# Peripheral2.net
KiCad netlist of a schematic drawn in Altium Designer
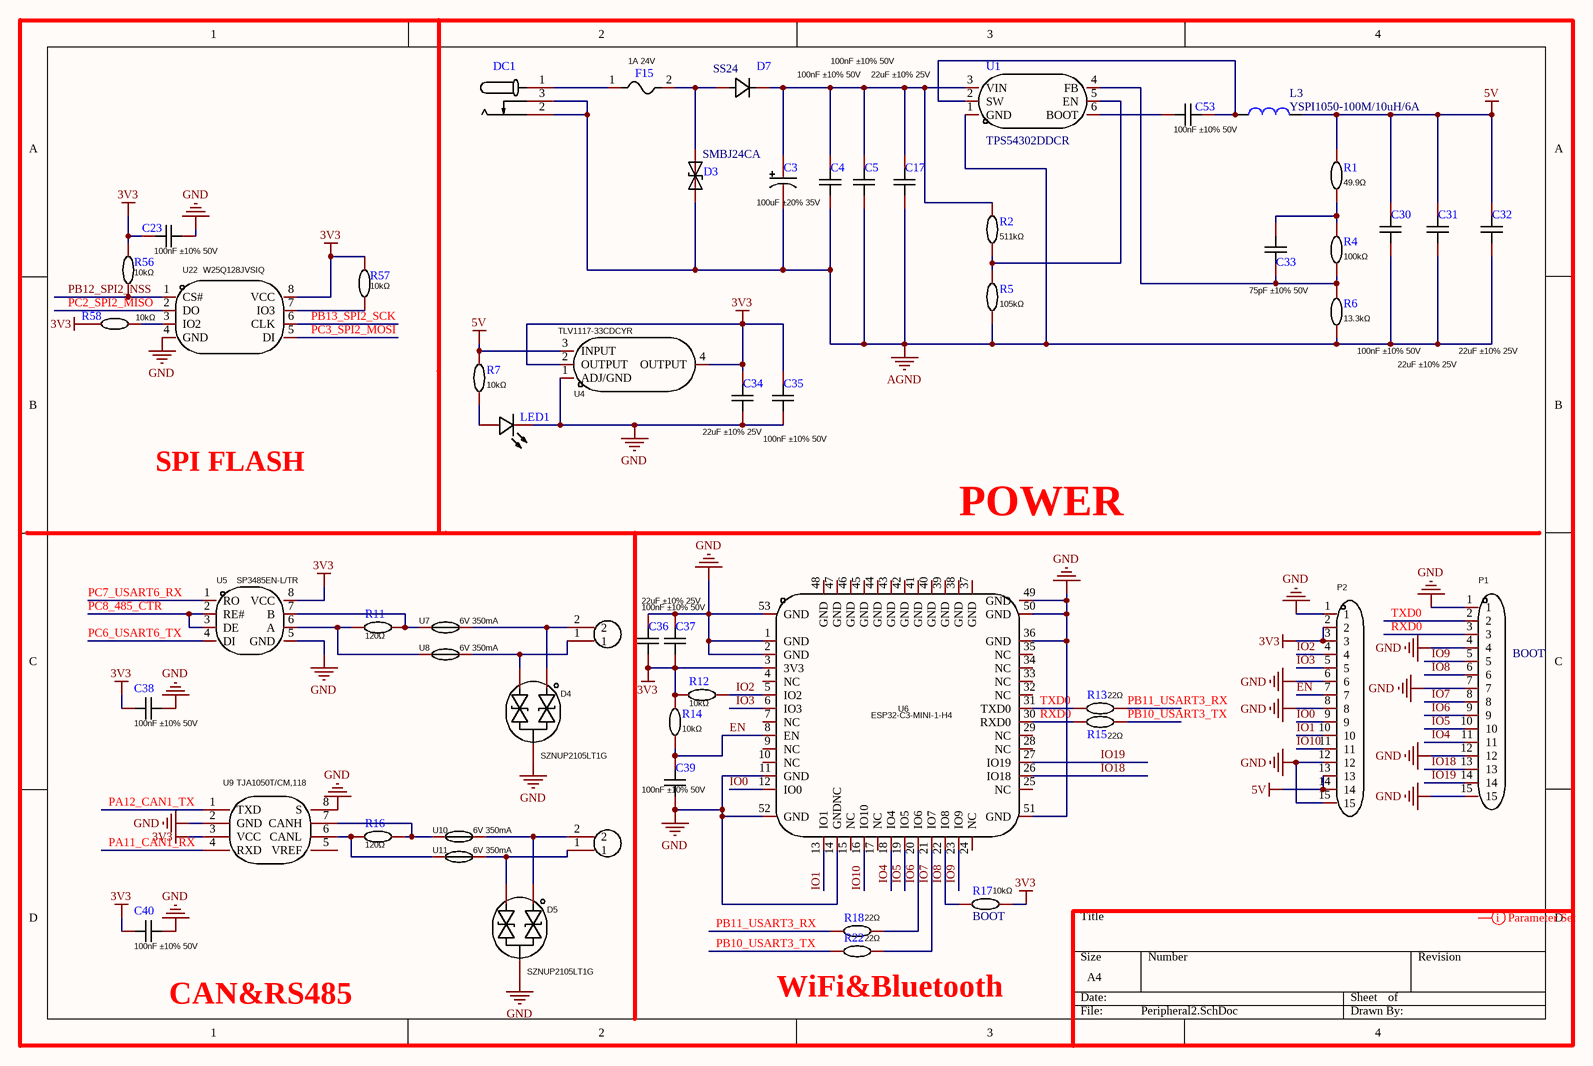
[diagram p0: Peripheral2.SchDoc]

(export (version "E")
  (design (tool "Eeschema 10.0.6"))
  (components
    (comp (ref "C3")
      (value "VES101M1VTR-0607")
      (footprint "CE 6.3*7.7")
      (fields
        (field (name "LCSC PART NAME") "100uF ±20% 35V")
        (field (name "MANUFACTURER") "lelon(立隆)")
        (field (name "TOLERANCE") "±20%")
      )
      (libsource (lib "altium-import") (part "root_0_VES101M1VTR-0607_"))
    )
    (comp (ref "C4")
      (value "CC0603KRX7R9BB104")
      (footprint "C0603")
      (fields
        (field (name "LCSC PART NAME") "100nF ±10% 50V")
        (field (name "MANUFACTURER") "YAGEO(国巨)")
        (field (name "TOLERANCE") "±10%")
      )
      (libsource (lib "altium-import") (part "root_1_CC0603KRX7R9BB104_"))
    )
    (comp (ref "C5")
      (value "CC0603KRX7R9BB104")
      (footprint "C0603")
      (fields
        (field (name "LCSC PART NAME") "100nF ±10% 50V")
        (field (name "MANUFACTURER") "YAGEO(国巨)")
        (field (name "TOLERANCE") "±10%")
      )
      (libsource (lib "altium-import") (part "root_1_CC0603KRX7R9BB104_"))
    )
    (comp (ref "C17")
      (value "CC0603KRX7R9BB104")
      (footprint "C1210")
      (fields
        (field (name "LCSC PART NAME") "22uF ±10% 25V")
        (field (name "MANUFACTURER") "YAGEO(国巨)")
        (field (name "TOLERANCE") "±10%")
      )
      (libsource (lib "altium-import") (part "root_1_CC0603KRX7R9BB104_"))
    )
    (comp (ref "C23")
      (value "CC0603KRX7R9BB104")
      (footprint "C0603")
      (fields
        (field (name "LCSC PART NAME") "100nF ±10% 50V")
        (field (name "MANUFACTURER") "YAGEO(国巨)")
        (field (name "TOLERANCE") "±10%")
      )
      (libsource (lib "altium-import") (part "root_2_CC0603KRX7R9BB104_"))
    )
    (comp (ref "C30")
      (value "CC0603KRX7R9BB104")
      (footprint "C0603")
      (fields
        (field (name "LCSC PART NAME") "100nF ±10% 50V")
        (field (name "MANUFACTURER") "YAGEO(国巨)")
        (field (name "TOLERANCE") "±10%")
      )
      (libsource (lib "altium-import") (part "root_1_CC0603KRX7R9BB104_"))
    )
    (comp (ref "C31")
      (value "CC0603KRX7R9BB104")
      (footprint "C1210")
      (fields
        (field (name "LCSC PART NAME") "22uF ±10% 25V")
        (field (name "MANUFACTURER") "YAGEO(国巨)")
        (field (name "TOLERANCE") "±10%")
      )
      (libsource (lib "altium-import") (part "root_1_CC0603KRX7R9BB104_"))
    )
    (comp (ref "C32")
      (value "CC0603KRX7R9BB104")
      (footprint "C1210")
      (fields
        (field (name "LCSC PART NAME") "22uF ±10% 25V")
        (field (name "MANUFACTURER") "YAGEO(国巨)")
        (field (name "TOLERANCE") "±10%")
      )
      (libsource (lib "altium-import") (part "root_1_CC0603KRX7R9BB104_"))
    )
    (comp (ref "C33")
      (value "CC0603KRX7R9BB104")
      (footprint "C0603")
      (fields
        (field (name "LCSC PART NAME") "75pF ±10% 50V")
        (field (name "MANUFACTURER") "YAGEO(国巨)")
        (field (name "TOLERANCE") "±10%")
      )
      (libsource (lib "altium-import") (part "root_1_CC0603KRX7R9BB104_"))
    )
    (comp (ref "C34")
      (value "CC0603KRX7R9BB104")
      (footprint "C1210")
      (fields
        (field (name "LCSC PART NAME") "22uF ±10% 25V")
        (field (name "MANUFACTURER") "YAGEO(国巨)")
        (field (name "TOLERANCE") "±10%")
      )
      (libsource (lib "altium-import") (part "root_1_CC0603KRX7R9BB104_"))
    )
    (comp (ref "C35")
      (value "CC0603KRX7R9BB104")
      (footprint "C0603")
      (fields
        (field (name "LCSC PART NAME") "100nF ±10% 50V")
        (field (name "MANUFACTURER") "YAGEO(国巨)")
        (field (name "TOLERANCE") "±10%")
      )
      (libsource (lib "altium-import") (part "root_1_CC0603KRX7R9BB104_"))
    )
    (comp (ref "C36")
      (value "CC0603KRX7R9BB104")
      (footprint "C1210")
      (fields
        (field (name "LCSC PART NAME") "22uF ±10% 25V")
        (field (name "MANUFACTURER") "YAGEO(国巨)")
        (field (name "TOLERANCE") "±10%")
      )
      (libsource (lib "altium-import") (part "root_1_CC0603KRX7R9BB104_"))
    )
    (comp (ref "C37")
      (value "CC0603KRX7R9BB104")
      (footprint "C0603")
      (fields
        (field (name "LCSC PART NAME") "100nF ±10% 50V")
        (field (name "MANUFACTURER") "YAGEO(国巨)")
        (field (name "TOLERANCE") "±10%")
      )
      (libsource (lib "altium-import") (part "root_1_CC0603KRX7R9BB104_"))
    )
    (comp (ref "C38")
      (value "CC0603KRX7R9BB104")
      (footprint "C0603")
      (fields
        (field (name "LCSC PART NAME") "100nF ±10% 50V")
        (field (name "MANUFACTURER") "YAGEO(国巨)")
        (field (name "TOLERANCE") "±10%")
      )
      (libsource (lib "altium-import") (part "root_2_CC0603KRX7R9BB104_"))
    )
    (comp (ref "C39")
      (value "CC0603KRX7R9BB104")
      (footprint "C0603")
      (fields
        (field (name "LCSC PART NAME") "100nF ±10% 50V")
        (field (name "MANUFACTURER") "YAGEO(国巨)")
        (field (name "TOLERANCE") "±10%")
      )
      (libsource (lib "altium-import") (part "root_1_CC0603KRX7R9BB104_"))
    )
    (comp (ref "C40")
      (value "CC0603KRX7R9BB104")
      (footprint "C0603")
      (fields
        (field (name "LCSC PART NAME") "100nF ±10% 50V")
        (field (name "MANUFACTURER") "YAGEO(国巨)")
        (field (name "TOLERANCE") "±10%")
      )
      (libsource (lib "altium-import") (part "root_2_CC0603KRX7R9BB104_"))
    )
    (comp (ref "C53")
      (value "CC0603KRX7R9BB104")
      (footprint "C0603")
      (fields
        (field (name "LCSC PART NAME") "100nF ±10% 50V")
        (field (name "MANUFACTURER") "YAGEO(国巨)")
        (field (name "TOLERANCE") "±10%")
      )
      (libsource (lib "altium-import") (part "root_2_CC0603KRX7R9BB104_"))
    )
    (comp (ref "CN1")
      (value "XH-2A_C20079")
      (footprint "XH2.5-2")
      (fields (field (name "MANUFACTURER") "BOOMELE(博穆精密)") (field (name "MANUFACTURER PART") "XH-2A"))
      (libsource (lib "altium-import") (part "root_2_XH-2A_C20079_"))
    )
    (comp (ref "CN2")
      (value "XH-2A_C20079")
      (footprint "XH2.5-2")
      (fields (field (name "MANUFACTURER") "BOOMELE(博穆精密)") (field (name "MANUFACTURER PART") "XH-2A"))
      (libsource (lib "altium-import") (part "root_2_XH-2A_C20079_"))
    )
    (comp (ref "D3")
      (value "SMBJ24CA")
      (footprint "SMB")
      (fields (field (name "MANUFACTURER") "Brightking(君耀电子)"))
      (libsource (lib "altium-import") (part "root_1_SMBJ24CA_C78416_"))
    )
    (comp (ref "D4")
      (value "SZNUP2105LT1G")
      (footprint "SOT-23")
      (fields (field (name "NAME") "SZNUP2105LT1G") (field (name "MANUFACTURER") "onsemi(安森美)"))
      (libsource (lib "altium-import") (part "root_2_SZNUP2105LT1G_"))
    )
    (comp (ref "D5")
      (value "SZNUP2105LT1G")
      (footprint "SOT-23")
      (fields (field (name "NAME") "SZNUP2105LT1G") (field (name "MANUFACTURER") "onsemi(安森美)"))
      (libsource (lib "altium-import") (part "root_2_SZNUP2105LT1G_"))
    )
    (comp (ref "D7")
      (value "SS24")
      (footprint "SMA")
      (fields (field (name "MANUFACTURER") "CJ(江苏长电/长晶)"))
      (libsource (lib "altium-import") (part "root_2_SS24_C2829443_"))
    )
    (comp (ref "DC1")
      (value "DC-005-25A")
      (footprint "DC-005")
      (fields (field (name "MANUFACTURER") "韩国韩荣"))
      (libsource (lib "altium-import") (part "root_0_DC-005-25A_"))
    )
    (comp (ref "F15")
      (value "TLC-NSMD100/24")
      (footprint "F1206")
      (fields (field (name "LCSC PART NAME") "1A 24V") (field (name "MANUFACTURER") "TLC(竞沃)"))
      (libsource (lib "altium-import") (part "root_0_TLC-NSMD100/24_"))
    )
    (comp (ref "L3")
      (value "YSPI1050-100M/10uH/6A")
      (footprint "IND-SMD_L11.5-W10.0_SMMS1040")
      (libsource (lib "*") (part "INDUCTOR"))
    )
    (comp (ref "LED1")
      (value "17-21SYGC/S530-E3/TR8")
      (footprint "LED 0805G")
      (fields (field (name "MANUFACTURER") "EVERLIGHT(亿光)"))
      (libsource (lib "altium-import") (part "root_2_17-21SYGC/S530-E3/TR8_"))
    )
    (comp (ref "P1")
      (value "KH-2.54FH-1X15P-H8.5")
      (footprint "HDR2.54-M-LI-15P")
      (fields (field (name "MANUFACTURER") "kinghelm(金航标)"))
      (libsource (lib "altium-import") (part "root_0_KH-2.54FH-1X15P-H8.5_"))
    )
    (comp (ref "P2")
      (value "KH-2.54FH-1X15P-H8.5")
      (footprint "HDR2.54-M-LI-15P")
      (fields (field (name "MANUFACTURER") "kinghelm(金航标)"))
      (libsource (lib "altium-import") (part "root_0_KH-2.54FH-1X15P-H8.5_"))
    )
    (comp (ref "R1")
      (value "49.9Ω")
      (footprint "R0603")
      (fields
        (field (name "MANUFACTURER") "UNI-ROYAL(厚声)")
        (field (name "MANUFACTURER PART") "0603WAF5113T5E")
        (field (name "TOLERANCE") "±1%")
      )
      (libsource (lib "altium-import") (part "root_1_0603WAF5113T5E_"))
    )
    (comp (ref "R2")
      (value "511kΩ")
      (footprint "R0603")
      (fields
        (field (name "MANUFACTURER") "UNI-ROYAL(厚声)")
        (field (name "MANUFACTURER PART") "0603WAF5113T5E")
        (field (name "TOLERANCE") "±1%")
      )
      (libsource (lib "altium-import") (part "root_1_0603WAF5113T5E_"))
    )
    (comp (ref "R4")
      (value "100kΩ")
      (footprint "R0603")
      (fields
        (field (name "MANUFACTURER") "UNI-ROYAL(厚声)")
        (field (name "MANUFACTURER PART") "0603WAF5113T5E")
        (field (name "TOLERANCE") "±1%")
      )
      (libsource (lib "altium-import") (part "root_1_0603WAF5113T5E_"))
    )
    (comp (ref "R5")
      (value "105kΩ")
      (footprint "R0603")
      (fields
        (field (name "MANUFACTURER") "UNI-ROYAL(厚声)")
        (field (name "MANUFACTURER PART") "0603WAF5113T5E")
        (field (name "TOLERANCE") "±1%")
      )
      (libsource (lib "altium-import") (part "root_1_0603WAF5113T5E_"))
    )
    (comp (ref "R6")
      (value "13.3kΩ")
      (footprint "R0603")
      (fields
        (field (name "MANUFACTURER") "UNI-ROYAL(厚声)")
        (field (name "MANUFACTURER PART") "0603WAF5113T5E")
        (field (name "TOLERANCE") "±1%")
      )
      (libsource (lib "altium-import") (part "root_1_0603WAF5113T5E_"))
    )
    (comp (ref "R7")
      (value "10kΩ")
      (footprint "R0603")
      (fields
        (field (name "MANUFACTURER") "UNI-ROYAL(厚声)")
        (field (name "MANUFACTURER PART") "0603WAF5113T5E")
        (field (name "TOLERANCE") "±1%")
      )
      (libsource (lib "altium-import") (part "root_1_0603WAF5113T5E_"))
    )
    (comp (ref "R11")
      (value "120Ω")
      (footprint "R0603")
      (fields
        (field (name "MANUFACTURER") "UNI-ROYAL(厚声)")
        (field (name "MANUFACTURER PART") "0603WAF5113T5E")
        (field (name "TOLERANCE") "±1%")
      )
      (libsource (lib "altium-import") (part "root_2_0603WAF5113T5E_"))
    )
    (comp (ref "R12")
      (value "10kΩ")
      (footprint "R0603")
      (fields
        (field (name "MANUFACTURER") "UNI-ROYAL(厚声)")
        (field (name "MANUFACTURER PART") "0603WAF5113T5E")
        (field (name "TOLERANCE") "±1%")
      )
      (libsource (lib "altium-import") (part "root_2_0603WAF5113T5E_"))
    )
    (comp (ref "R13")
      (value "22Ω")
      (footprint "R0603")
      (fields
        (field (name "MANUFACTURER") "UNI-ROYAL(厚声)")
        (field (name "MANUFACTURER PART") "0603WAF5113T5E")
        (field (name "TOLERANCE") "±1%")
      )
      (libsource (lib "altium-import") (part "root_2_0603WAF5113T5E_"))
    )
    (comp (ref "R14")
      (value "10kΩ")
      (footprint "R0603")
      (fields
        (field (name "MANUFACTURER") "UNI-ROYAL(厚声)")
        (field (name "MANUFACTURER PART") "0603WAF5113T5E")
        (field (name "TOLERANCE") "±1%")
      )
      (libsource (lib "altium-import") (part "root_1_0603WAF5113T5E_"))
    )
    (comp (ref "R15")
      (value "22Ω")
      (footprint "R0603")
      (fields
        (field (name "MANUFACTURER") "UNI-ROYAL(厚声)")
        (field (name "MANUFACTURER PART") "0603WAF5113T5E")
        (field (name "TOLERANCE") "±1%")
      )
      (libsource (lib "altium-import") (part "root_2_0603WAF5113T5E_"))
    )
    (comp (ref "R16")
      (value "120Ω")
      (footprint "R0603")
      (fields
        (field (name "MANUFACTURER") "UNI-ROYAL(厚声)")
        (field (name "MANUFACTURER PART") "0603WAF5113T5E")
        (field (name "TOLERANCE") "±1%")
      )
      (libsource (lib "altium-import") (part "root_2_0603WAF5113T5E_"))
    )
    (comp (ref "R17")
      (value "10kΩ")
      (footprint "R0603")
      (fields
        (field (name "MANUFACTURER") "UNI-ROYAL(厚声)")
        (field (name "MANUFACTURER PART") "0603WAF5113T5E")
        (field (name "TOLERANCE") "±1%")
      )
      (libsource (lib "altium-import") (part "root_2_0603WAF5113T5E_"))
    )
    (comp (ref "R18")
      (value "22Ω")
      (footprint "R0603")
      (fields
        (field (name "MANUFACTURER") "UNI-ROYAL(厚声)")
        (field (name "MANUFACTURER PART") "0603WAF5113T5E")
        (field (name "TOLERANCE") "±1%")
      )
      (libsource (lib "altium-import") (part "root_2_0603WAF5113T5E_"))
    )
    (comp (ref "R22")
      (value "22Ω")
      (footprint "R0603")
      (fields
        (field (name "MANUFACTURER") "UNI-ROYAL(厚声)")
        (field (name "MANUFACTURER PART") "0603WAF5113T5E")
        (field (name "TOLERANCE") "±1%")
      )
      (libsource (lib "altium-import") (part "root_2_0603WAF5113T5E_"))
    )
    (comp (ref "R56")
      (value "10kΩ")
      (footprint "R0603")
      (fields
        (field (name "MANUFACTURER") "UNI-ROYAL(厚声)")
        (field (name "MANUFACTURER PART") "0603WAF5113T5E")
        (field (name "TOLERANCE") "±1%")
      )
      (libsource (lib "altium-import") (part "root_3_0603WAF5113T5E_"))
    )
    (comp (ref "R57")
      (value "10kΩ")
      (footprint "R0603")
      (fields
        (field (name "MANUFACTURER") "UNI-ROYAL(厚声)")
        (field (name "MANUFACTURER PART") "0603WAF5113T5E")
        (field (name "TOLERANCE") "±1%")
      )
      (libsource (lib "altium-import") (part "root_3_0603WAF5113T5E_"))
    )
    (comp (ref "R58")
      (value "10kΩ")
      (footprint "R0603")
      (fields
        (field (name "MANUFACTURER") "UNI-ROYAL(厚声)")
        (field (name "MANUFACTURER PART") "0603WAF5113T5E")
        (field (name "TOLERANCE") "±1%")
      )
      (libsource (lib "altium-import") (part "root_2_0603WAF5113T5E_"))
    )
    (comp (ref "U1")
      (value "TPS54302DDCR")
      (footprint "SOT23-6")
      (fields (field (name "MANUFACTURER") "TI(德州仪器)"))
      (libsource (lib "altium-import") (part "root_2_mirrored_TPS54302DDCR_"))
    )
    (comp (ref "U4")
      (value "TLV1117-33CDCYR")
      (footprint "SOT223")
      (fields (field (name "NAME") "TLV1117-33CDCYR") (field (name "MANUFACTURER") "TI(德州仪器)"))
      (libsource (lib "altium-import") (part "root_1_mirrored_TLV1117-33CDCYR_"))
    )
    (comp (ref "U5")
      (value "SP3485EN-L/TR")
      (footprint "SOP8_SP3485")
      (fields (field (name "NAME") "SP3485EN-L/TR") (field (name "MANUFACTURER") "MaxLinear"))
      (libsource (lib "altium-import") (part "root_0_SP3485EN-L/TR_"))
    )
    (comp (ref "U6")
      (value "ESP32-C3-MINI-1-H4")
      (footprint "WIFIM-SMD_ESP32-C3-MINI-1")
      (fields (field (name "NAME") "ESP32-C3-MINI-1-H4") (field (name "MANUFACTURER") "ESPRESSIF(乐鑫)"))
      (libsource (lib "altium-import") (part "root_0_ESP32-C3-MINI-1U-H4_"))
    )
    (comp (ref "U7")
      (value "0603L035YR")
      (footprint "F0603")
      (fields (field (name "LCSC PART NAME") "6V 350mA") (field (name "MANUFACTURER") "Littelfuse(美国力特)"))
      (libsource (lib "altium-import") (part "root_0_0603L035YR_"))
    )
    (comp (ref "U8")
      (value "0603L035YR")
      (footprint "F0603")
      (fields (field (name "LCSC PART NAME") "6V 350mA") (field (name "MANUFACTURER") "Littelfuse(美国力特)"))
      (libsource (lib "altium-import") (part "root_0_0603L035YR_"))
    )
    (comp (ref "U9")
      (value "TJA1050T/CM,118")
      (footprint "SOP8_TJA1050")
      (fields (field (name "NAME") "TJA1050T/CM,118") (field (name "MANUFACTURER") "NXP(恩智浦)"))
      (libsource (lib "altium-import") (part "root_0_TJA1050T/CM,118_"))
    )
    (comp (ref "U10")
      (value "0603L035YR")
      (footprint "F0603")
      (fields (field (name "LCSC PART NAME") "6V 350mA") (field (name "MANUFACTURER") "Littelfuse(美国力特)"))
      (libsource (lib "altium-import") (part "root_0_0603L035YR_"))
    )
    (comp (ref "U11")
      (value "0603L035YR")
      (footprint "F0603")
      (fields (field (name "LCSC PART NAME") "6V 350mA") (field (name "MANUFACTURER") "Littelfuse(美国力特)"))
      (libsource (lib "altium-import") (part "root_0_0603L035YR_"))
    )
    (comp (ref "U22")
      (value "W25Q128JVSIQ")
      (footprint "SOIC8")
      (fields (field (name "NAME") "W25Q128JVSIQ") (field (name "MANUFACTURER") "WINBOND(华邦)"))
      (libsource (lib "altium-import") (part "root_0_W25Q128JVSIQ_"))
    )
  )
  (nets
    (net (code "1") (name "/EN") (class "Default")
      (node (ref "C39") (pin "2") (pinfunction "2_2") (pintype "passive"))
      (node (ref "P2") (pin "7") (pinfunction "7_7") (pintype "passive"))
      (node (ref "R14") (pin "1") (pinfunction "1_1") (pintype "passive"))
      (node (ref "U6") (pin "8") (pinfunction "EN_8") (pintype "passive"))
    )
    (net (code "2") (name "/IO0") (class "Default")
      (node (ref "P2") (pin "9") (pinfunction "9_9") (pintype "passive"))
      (node (ref "U6") (pin "12") (pinfunction "IO0_12") (pintype "passive"))
    )
    (net (code "3") (name "/IO1") (class "Default")
      (node (ref "P2") (pin "10") (pinfunction "10_10") (pintype "passive"))
      (node (ref "U6") (pin "13") (pinfunction "IO1_13") (pintype "passive"))
    )
    (net (code "4") (name "/IO2") (class "Default")
      (node (ref "P2") (pin "4") (pinfunction "4_4") (pintype "passive"))
      (node (ref "R12") (pin "1") (pinfunction "1_1") (pintype "passive"))
      (node (ref "U6") (pin "5") (pinfunction "IO2_5") (pintype "passive"))
    )
    (net (code "5") (name "/IO3") (class "Default")
      (node (ref "P2") (pin "5") (pinfunction "5_5") (pintype "passive"))
      (node (ref "U6") (pin "6") (pinfunction "IO3_6") (pintype "passive"))
    )
    (net (code "6") (name "/IO4") (class "Default")
      (node (ref "P1") (pin "11") (pinfunction "11_11") (pintype "passive"))
      (node (ref "U6") (pin "18") (pinfunction "IO4_18") (pintype "passive"))
    )
    (net (code "7") (name "/IO5") (class "Default")
      (node (ref "P1") (pin "10") (pinfunction "10_10") (pintype "passive"))
      (node (ref "U6") (pin "19") (pinfunction "IO5_19") (pintype "passive"))
    )
    (net (code "8") (name "/IO6") (class "Default")
      (node (ref "P1") (pin "9") (pinfunction "9_9") (pintype "passive"))
      (node (ref "R18") (pin "1") (pinfunction "1_1") (pintype "passive"))
      (node (ref "U6") (pin "20") (pinfunction "IO6_20") (pintype "passive"))
    )
    (net (code "9") (name "/IO7") (class "Default")
      (node (ref "P1") (pin "8") (pinfunction "8_8") (pintype "passive"))
      (node (ref "R22") (pin "1") (pinfunction "1_1") (pintype "passive"))
      (node (ref "U6") (pin "21") (pinfunction "IO7_21") (pintype "passive"))
    )
    (net (code "10") (name "/IO8") (class "Default")
      (node (ref "P1") (pin "6") (pinfunction "6_6") (pintype "passive"))
      (node (ref "R17") (pin "2") (pinfunction "2_2") (pintype "passive"))
      (node (ref "U6") (pin "22") (pinfunction "IO8_22") (pintype "passive"))
    )
    (net (code "11") (name "/IO9") (class "Default")
      (node (ref "P1") (pin "5") (pinfunction "5_5") (pintype "passive"))
      (node (ref "U6") (pin "23") (pinfunction "IO9_23") (pintype "passive"))
    )
    (net (code "12") (name "/IO10") (class "Default")
      (node (ref "P2") (pin "11") (pinfunction "11_11") (pintype "passive"))
      (node (ref "U6") (pin "16") (pinfunction "IO10_16") (pintype "passive"))
    )
    (net (code "13") (name "/IO18") (class "Default")
      (node (ref "P1") (pin "13") (pinfunction "13_13") (pintype "passive"))
      (node (ref "U6") (pin "26") (pinfunction "IO18_26") (pintype "passive"))
    )
    (net (code "14") (name "/IO19") (class "Default")
      (node (ref "P1") (pin "14") (pinfunction "14_14") (pintype "passive"))
      (node (ref "U6") (pin "27") (pinfunction "IO19_27") (pintype "passive"))
    )
    (net (code "15") (name "/PA11_CAN1_RX") (class "Default")
      (node (ref "U9") (pin "4") (pinfunction "RXD_4") (pintype "passive"))
    )
    (net (code "16") (name "/PA12_CAN1_TX") (class "Default")
      (node (ref "U9") (pin "1") (pinfunction "TXD_1") (pintype "passive"))
    )
    (net (code "17") (name "/PB10_USART3_TX") (class "Default")
      (node (ref "R15") (pin "1") (pinfunction "1_1") (pintype "passive"))
      (node (ref "R22") (pin "2") (pinfunction "2_2") (pintype "passive"))
    )
    (net (code "18") (name "/PB11_USART3_RX") (class "Default")
      (node (ref "R13") (pin "1") (pinfunction "1_1") (pintype "passive"))
      (node (ref "R18") (pin "2") (pinfunction "2_2") (pintype "passive"))
    )
    (net (code "19") (name "/PB12_SPI2_NSS") (class "Default")
      (node (ref "R56") (pin "2") (pinfunction "2_2") (pintype "passive"))
      (node (ref "U22") (pin "1") (pinfunction "CS#_1") (pintype "passive"))
    )
    (net (code "20") (name "/PB13_SPI2_SCK") (class "Default")
      (node (ref "U22") (pin "6") (pinfunction "CLK_6") (pintype "passive"))
    )
    (net (code "21") (name "/PC2_SPI2_MISO") (class "Default")
      (node (ref "U22") (pin "2") (pinfunction "DO_2") (pintype "passive"))
    )
    (net (code "22") (name "/PC3_SPI2_MOSI") (class "Default")
      (node (ref "U22") (pin "5") (pinfunction "DI_5") (pintype "passive"))
    )
    (net (code "23") (name "/PC6_USART6_TX") (class "Default")
      (node (ref "U5") (pin "4") (pinfunction "DI_4") (pintype "passive"))
    )
    (net (code "24") (name "/PC7_USART6_RX") (class "Default")
      (node (ref "U5") (pin "1") (pinfunction "RO_1") (pintype "passive"))
    )
    (net (code "25") (name "/PC8_485_CTR") (class "Default")
      (node (ref "U5") (pin "2") (pinfunction "RE#_2") (pintype "passive"))
      (node (ref "U5") (pin "3") (pinfunction "DE_3") (pintype "passive"))
    )
    (net (code "26") (name "/RXD0") (class "Default")
      (node (ref "P1") (pin "3") (pinfunction "3_3") (pintype "passive"))
      (node (ref "R15") (pin "2") (pinfunction "2_2") (pintype "passive"))
      (node (ref "U6") (pin "30") (pinfunction "RXD0_30") (pintype "passive"))
    )
    (net (code "27") (name "/TXD0") (class "Default")
      (node (ref "P1") (pin "2") (pinfunction "2_2") (pintype "passive"))
      (node (ref "R13") (pin "2") (pinfunction "2_2") (pintype "passive"))
      (node (ref "U6") (pin "31") (pinfunction "TXD0_31") (pintype "passive"))
    )
    (net (code "28") (name "3V3") (class "Default")
      (node (ref "C23") (pin "2") (pinfunction "2_2") (pintype "passive"))
      (node (ref "C34") (pin "2") (pinfunction "2_2") (pintype "passive"))
      (node (ref "C35") (pin "2") (pinfunction "2_2") (pintype "passive"))
      (node (ref "C36") (pin "1") (pinfunction "1_1") (pintype "passive"))
      (node (ref "C37") (pin "1") (pinfunction "1_1") (pintype "passive"))
      (node (ref "C38") (pin "2") (pinfunction "2_2") (pintype "passive"))
      (node (ref "C40") (pin "2") (pinfunction "2_2") (pintype "passive"))
      (node (ref "P2") (pin "2") (pinfunction "2_2") (pintype "passive"))
      (node (ref "P2") (pin "3") (pinfunction "3_3") (pintype "passive"))
      (node (ref "R12") (pin "2") (pinfunction "2_2") (pintype "passive"))
      (node (ref "R14") (pin "2") (pinfunction "2_2") (pintype "passive"))
      (node (ref "R17") (pin "1") (pinfunction "1_1") (pintype "passive"))
      (node (ref "R56") (pin "1") (pinfunction "1_1") (pintype "passive"))
      (node (ref "R57") (pin "1") (pinfunction "1_1") (pintype "passive"))
      (node (ref "R58") (pin "2") (pinfunction "2_2") (pintype "passive"))
      (node (ref "U22") (pin "8") (pinfunction "VCC_8") (pintype "passive"))
      (node (ref "U4") (pin "2") (pinfunction "OUTPUT_2") (pintype "passive"))
      (node (ref "U4") (pin "4") (pinfunction "OUTPUT_4") (pintype "passive"))
      (node (ref "U5") (pin "8") (pinfunction "VCC_8") (pintype "passive"))
      (node (ref "U6") (pin "3") (pinfunction "3V3_3") (pintype "passive"))
      (node (ref "U9") (pin "3") (pinfunction "VCC_3") (pintype "passive"))
    )
    (net (code "29") (name "5V") (class "Default")
      (node (ref "C30") (pin "2") (pinfunction "2_2") (pintype "passive"))
      (node (ref "C31") (pin "2") (pinfunction "2_2") (pintype "passive"))
      (node (ref "C32") (pin "2") (pinfunction "2_2") (pintype "passive"))
      (node (ref "L3") (pin "2") (pinfunction "2_2") (pintype "passive"))
      (node (ref "P2") (pin "13") (pinfunction "13_13") (pintype "passive"))
      (node (ref "P2") (pin "14") (pinfunction "14_14") (pintype "passive"))
      (node (ref "R1") (pin "2") (pinfunction "2_2") (pintype "passive"))
      (node (ref "R7") (pin "2") (pinfunction "2_2") (pintype "passive"))
      (node (ref "U4") (pin "3") (pinfunction "INPUT_3") (pintype "passive"))
    )
    (net (code "30") (name "AGND") (class "Default")
      (node (ref "C17") (pin "1") (pinfunction "1_1") (pintype "passive"))
      (node (ref "C3") (pin "2") (pinfunction "2_2") (pintype "passive"))
      (node (ref "C30") (pin "1") (pinfunction "1_1") (pintype "passive"))
      (node (ref "C31") (pin "1") (pinfunction "1_1") (pintype "passive"))
      (node (ref "C32") (pin "1") (pinfunction "1_1") (pintype "passive"))
      (node (ref "C4") (pin "1") (pinfunction "1_1") (pintype "passive"))
      (node (ref "C5") (pin "1") (pinfunction "1_1") (pintype "passive"))
      (node (ref "D3") (pin "2") (pinfunction "A_2") (pintype "passive"))
      (node (ref "DC1") (pin "2") (pinfunction "2_2") (pintype "passive"))
      (node (ref "DC1") (pin "3") (pinfunction "3_3") (pintype "passive"))
      (node (ref "R5") (pin "1") (pinfunction "1_1") (pintype "passive"))
      (node (ref "R6") (pin "1") (pinfunction "1_1") (pintype "passive"))
      (node (ref "U1") (pin "1") (pinfunction "GND_1") (pintype "passive"))
    )
    (net (code "31") (name "GND") (class "Default")
      (node (ref "C23") (pin "1") (pinfunction "1_1") (pintype "passive"))
      (node (ref "C34") (pin "1") (pinfunction "1_1") (pintype "passive"))
      (node (ref "C35") (pin "1") (pinfunction "1_1") (pintype "passive"))
      (node (ref "C36") (pin "2") (pinfunction "2_2") (pintype "passive"))
      (node (ref "C37") (pin "2") (pinfunction "2_2") (pintype "passive"))
      (node (ref "C38") (pin "1") (pinfunction "1_1") (pintype "passive"))
      (node (ref "C39") (pin "1") (pinfunction "1_1") (pintype "passive"))
      (node (ref "C40") (pin "1") (pinfunction "1_1") (pintype "passive"))
      (node (ref "D4") (pin "3") (pinfunction "3_3") (pintype "passive"))
      (node (ref "D5") (pin "3") (pinfunction "3_3") (pintype "passive"))
      (node (ref "LED1") (pin "1") (pinfunction "K_1") (pintype "passive"))
      (node (ref "P1") (pin "1") (pinfunction "1_1") (pintype "passive"))
      (node (ref "P1") (pin "12") (pinfunction "12_12") (pintype "passive"))
      (node (ref "P1") (pin "15") (pinfunction "15_15") (pintype "passive"))
      (node (ref "P1") (pin "4") (pinfunction "4_4") (pintype "passive"))
      (node (ref "P1") (pin "7") (pinfunction "7_7") (pintype "passive"))
      (node (ref "P2") (pin "1") (pinfunction "1_1") (pintype "passive"))
      (node (ref "P2") (pin "12") (pinfunction "12_12") (pintype "passive"))
      (node (ref "P2") (pin "15") (pinfunction "15_15") (pintype "passive"))
      (node (ref "P2") (pin "6") (pinfunction "6_6") (pintype "passive"))
      (node (ref "P2") (pin "8") (pinfunction "8_8") (pintype "passive"))
      (node (ref "U22") (pin "4") (pinfunction "GND_4") (pintype "passive"))
      (node (ref "U4") (pin "1") (pinfunction "ADJ/GND_1") (pintype "passive"))
      (node (ref "U5") (pin "5") (pinfunction "GND_5") (pintype "passive"))
      (node (ref "U6") (pin "1") (pinfunction "GND_1") (pintype "passive"))
      (node (ref "U6") (pin "11") (pinfunction "GND_11") (pintype "passive"))
      (node (ref "U6") (pin "14") (pinfunction "GNDNC_14") (pintype "passive"))
      (node (ref "U6") (pin "2") (pinfunction "GND_2") (pintype "passive"))
      (node (ref "U6") (pin "36") (pinfunction "GND_36") (pintype "passive"))
      (node (ref "U6") (pin "49") (pinfunction "GND_49") (pintype "passive"))
      (node (ref "U6") (pin "50") (pinfunction "GND_50") (pintype "passive"))
      (node (ref "U6") (pin "51") (pinfunction "GND_51") (pintype "passive"))
      (node (ref "U6") (pin "52") (pinfunction "GND_52") (pintype "passive"))
      (node (ref "U6") (pin "53") (pinfunction "GND_53") (pintype "passive"))
      (node (ref "U9") (pin "2") (pinfunction "GND_2") (pintype "passive"))
      (node (ref "U9") (pin "8") (pinfunction "S_8") (pintype "passive"))
    )
    (net (code "32") (name "Net-(C33-Pad2)") (class "Default")
      (node (ref "C33") (pin "2") (pinfunction "2_2") (pintype "passive"))
      (node (ref "R1") (pin "1") (pinfunction "1_1") (pintype "passive"))
      (node (ref "R4") (pin "2") (pinfunction "2_2") (pintype "passive"))
    )
    (net (code "33") (name "Net-(CN1-Pad1)") (class "Default")
      (node (ref "CN1") (pin "1") (pinfunction "1_1") (pintype "passive"))
      (node (ref "D4") (pin "2") (pinfunction "2_2") (pintype "passive"))
      (node (ref "U8") (pin "2") (pinfunction "2_2") (pintype "passive"))
    )
    (net (code "34") (name "Net-(CN1-Pad2)") (class "Default")
      (node (ref "CN1") (pin "2") (pinfunction "2_2") (pintype "passive"))
      (node (ref "D4") (pin "1") (pinfunction "1_1") (pintype "passive"))
      (node (ref "U7") (pin "2") (pinfunction "2_2") (pintype "passive"))
    )
    (net (code "35") (name "Net-(CN2-Pad1)") (class "Default")
      (node (ref "CN2") (pin "1") (pinfunction "1_1") (pintype "passive"))
      (node (ref "D5") (pin "2") (pinfunction "2_2") (pintype "passive"))
      (node (ref "U11") (pin "2") (pinfunction "2_2") (pintype "passive"))
    )
    (net (code "36") (name "Net-(CN2-Pad2)") (class "Default")
      (node (ref "CN2") (pin "2") (pinfunction "2_2") (pintype "passive"))
      (node (ref "D5") (pin "1") (pinfunction "1_1") (pintype "passive"))
      (node (ref "U10") (pin "2") (pinfunction "2_2") (pintype "passive"))
    )
    (net (code "37") (name "Net-(D3-K)") (class "Default")
      (node (ref "D3") (pin "1") (pinfunction "K_1") (pintype "passive"))
      (node (ref "D7") (pin "2") (pinfunction "A_2") (pintype "passive"))
      (node (ref "F15") (pin "2") (pinfunction "2_2") (pintype "passive"))
    )
    (net (code "38") (name "Net-(D7-K)") (class "Default")
      (node (ref "C17") (pin "2") (pinfunction "2_2") (pintype "passive"))
      (node (ref "C3") (pin "1") (pinfunction "1_1") (pintype "passive"))
      (node (ref "C4") (pin "2") (pinfunction "2_2") (pintype "passive"))
      (node (ref "C5") (pin "2") (pinfunction "2_2") (pintype "passive"))
      (node (ref "D7") (pin "1") (pinfunction "K_1") (pintype "passive"))
      (node (ref "R2") (pin "2") (pinfunction "2_2") (pintype "passive"))
      (node (ref "U1") (pin "3") (pinfunction "VIN_3") (pintype "passive"))
    )
    (net (code "39") (name "Net-(DC1-Pad1)") (class "Default")
      (node (ref "DC1") (pin "1") (pinfunction "1_1") (pintype "passive"))
      (node (ref "F15") (pin "1") (pinfunction "1_1") (pintype "passive"))
    )
    (net (code "40") (name "Net-(LED1-A)") (class "Default")
      (node (ref "LED1") (pin "2") (pinfunction "A_2") (pintype "passive"))
      (node (ref "R7") (pin "1") (pinfunction "1_1") (pintype "passive"))
    )
    (net (code "41") (name "Net-(U1-BOOT)") (class "Default")
      (node (ref "C53") (pin "2") (pinfunction "2_2") (pintype "passive"))
      (node (ref "U1") (pin "6") (pinfunction "BOOT_6") (pintype "passive"))
    )
    (net (code "42") (name "Net-(U1-EN)") (class "Default")
      (node (ref "R2") (pin "1") (pinfunction "1_1") (pintype "passive"))
      (node (ref "R5") (pin "2") (pinfunction "2_2") (pintype "passive"))
      (node (ref "U1") (pin "5") (pinfunction "EN_5") (pintype "passive"))
    )
    (net (code "43") (name "Net-(U1-FB)") (class "Default")
      (node (ref "C33") (pin "1") (pinfunction "1_1") (pintype "passive"))
      (node (ref "R4") (pin "1") (pinfunction "1_1") (pintype "passive"))
      (node (ref "R6") (pin "2") (pinfunction "2_2") (pintype "passive"))
      (node (ref "U1") (pin "4") (pinfunction "FB_4") (pintype "passive"))
    )
    (net (code "44") (name "Net-(U1-SW)") (class "Default")
      (node (ref "C53") (pin "1") (pinfunction "1_1") (pintype "passive"))
      (node (ref "L3") (pin "1") (pinfunction "1_1") (pintype "passive"))
      (node (ref "U1") (pin "2") (pinfunction "SW_2") (pintype "passive"))
    )
    (net (code "45") (name "Net-(U5-A)") (class "Default")
      (node (ref "R11") (pin "2") (pinfunction "2_2") (pintype "passive"))
      (node (ref "U5") (pin "6") (pinfunction "A_6") (pintype "passive"))
      (node (ref "U8") (pin "1") (pinfunction "1_1") (pintype "passive"))
    )
    (net (code "46") (name "Net-(U5-B)") (class "Default")
      (node (ref "R11") (pin "1") (pinfunction "1_1") (pintype "passive"))
      (node (ref "U5") (pin "7") (pinfunction "B_7") (pintype "passive"))
      (node (ref "U7") (pin "1") (pinfunction "1_1") (pintype "passive"))
    )
    (net (code "47") (name "Net-(U9-CANH)") (class "Default")
      (node (ref "R16") (pin "1") (pinfunction "1_1") (pintype "passive"))
      (node (ref "U10") (pin "1") (pinfunction "1_1") (pintype "passive"))
      (node (ref "U9") (pin "7") (pinfunction "CANH_7") (pintype "passive"))
    )
    (net (code "48") (name "Net-(U9-CANL)") (class "Default")
      (node (ref "R16") (pin "2") (pinfunction "2_2") (pintype "passive"))
      (node (ref "U11") (pin "1") (pinfunction "1_1") (pintype "passive"))
      (node (ref "U9") (pin "6") (pinfunction "CANL_6") (pintype "passive"))
    )
    (net (code "49") (name "Net-(U22-IO2)") (class "Default")
      (node (ref "R58") (pin "1") (pinfunction "1_1") (pintype "passive"))
      (node (ref "U22") (pin "3") (pinfunction "IO2_3") (pintype "passive"))
    )
    (net (code "50") (name "Net-(U22-IO3)") (class "Default")
      (node (ref "R57") (pin "2") (pinfunction "2_2") (pintype "passive"))
      (node (ref "U22") (pin "7") (pinfunction "IO3_7") (pintype "passive"))
    )
    (net (code "51") (name "unconnected-(U6-GND-Pad37)") (class "Default")
      (node (ref "U6") (pin "37") (pinfunction "GND_37") (pintype "passive"))
    )
    (net (code "52") (name "unconnected-(U6-GND-Pad38)") (class "Default")
      (node (ref "U6") (pin "38") (pinfunction "GND_38") (pintype "passive"))
    )
    (net (code "53") (name "unconnected-(U6-GND-Pad39)") (class "Default")
      (node (ref "U6") (pin "39") (pinfunction "GND_39") (pintype "passive"))
    )
    (net (code "54") (name "unconnected-(U6-GND-Pad40)") (class "Default")
      (node (ref "U6") (pin "40") (pinfunction "GND_40") (pintype "passive"))
    )
    (net (code "55") (name "unconnected-(U6-GND-Pad41)") (class "Default")
      (node (ref "U6") (pin "41") (pinfunction "GND_41") (pintype "passive"))
    )
    (net (code "56") (name "unconnected-(U6-GND-Pad42)") (class "Default")
      (node (ref "U6") (pin "42") (pinfunction "GND_42") (pintype "passive"))
    )
    (net (code "57") (name "unconnected-(U6-GND-Pad43)") (class "Default")
      (node (ref "U6") (pin "43") (pinfunction "GND_43") (pintype "passive"))
    )
    (net (code "58") (name "unconnected-(U6-GND-Pad44)") (class "Default")
      (node (ref "U6") (pin "44") (pinfunction "GND_44") (pintype "passive"))
    )
    (net (code "59") (name "unconnected-(U6-GND-Pad45)") (class "Default")
      (node (ref "U6") (pin "45") (pinfunction "GND_45") (pintype "passive"))
    )
    (net (code "60") (name "unconnected-(U6-GND-Pad46)") (class "Default")
      (node (ref "U6") (pin "46") (pinfunction "GND_46") (pintype "passive"))
    )
    (net (code "61") (name "unconnected-(U6-GND-Pad47)") (class "Default")
      (node (ref "U6") (pin "47") (pinfunction "GND_47") (pintype "passive"))
    )
    (net (code "62") (name "unconnected-(U6-GND-Pad48)") (class "Default")
      (node (ref "U6") (pin "48") (pinfunction "GND_48") (pintype "passive"))
    )
    (net (code "63") (name "unconnected-(U6-NC-Pad4)") (class "Default")
      (node (ref "U6") (pin "4") (pinfunction "NC_4") (pintype "passive"))
    )
    (net (code "64") (name "unconnected-(U6-NC-Pad7)") (class "Default")
      (node (ref "U6") (pin "7") (pinfunction "NC_7") (pintype "passive"))
    )
    (net (code "65") (name "unconnected-(U6-NC-Pad9)") (class "Default")
      (node (ref "U6") (pin "9") (pinfunction "NC_9") (pintype "passive"))
    )
    (net (code "66") (name "unconnected-(U6-NC-Pad10)") (class "Default")
      (node (ref "U6") (pin "10") (pinfunction "NC_10") (pintype "passive"))
    )
    (net (code "67") (name "unconnected-(U6-NC-Pad15)") (class "Default")
      (node (ref "U6") (pin "15") (pinfunction "NC_15") (pintype "passive"))
    )
    (net (code "68") (name "unconnected-(U6-NC-Pad17)") (class "Default")
      (node (ref "U6") (pin "17") (pinfunction "NC_17") (pintype "passive"))
    )
    (net (code "69") (name "unconnected-(U6-NC-Pad24)") (class "Default")
      (node (ref "U6") (pin "24") (pinfunction "NC_24") (pintype "passive"))
    )
    (net (code "70") (name "unconnected-(U6-NC-Pad25)") (class "Default")
      (node (ref "U6") (pin "25") (pinfunction "NC_25") (pintype "passive"))
    )
    (net (code "71") (name "unconnected-(U6-NC-Pad28)") (class "Default")
      (node (ref "U6") (pin "28") (pinfunction "NC_28") (pintype "passive"))
    )
    (net (code "72") (name "unconnected-(U6-NC-Pad29)") (class "Default")
      (node (ref "U6") (pin "29") (pinfunction "NC_29") (pintype "passive"))
    )
    (net (code "73") (name "unconnected-(U6-NC-Pad32)") (class "Default")
      (node (ref "U6") (pin "32") (pinfunction "NC_32") (pintype "passive"))
    )
    (net (code "74") (name "unconnected-(U6-NC-Pad33)") (class "Default")
      (node (ref "U6") (pin "33") (pinfunction "NC_33") (pintype "passive"))
    )
    (net (code "75") (name "unconnected-(U6-NC-Pad34)") (class "Default")
      (node (ref "U6") (pin "34") (pinfunction "NC_34") (pintype "passive"))
    )
    (net (code "76") (name "unconnected-(U6-NC-Pad35)") (class "Default")
      (node (ref "U6") (pin "35") (pinfunction "NC_35") (pintype "passive"))
    )
    (net (code "77") (name "unconnected-(U9-VREF-Pad5)") (class "Default")
      (node (ref "U9") (pin "5") (pinfunction "VREF_5") (pintype "passive"))
    )
  )
)
